# LoRa_RFM98W_Shield.net
KiCad netlist of a schematic drawn in EAGLE
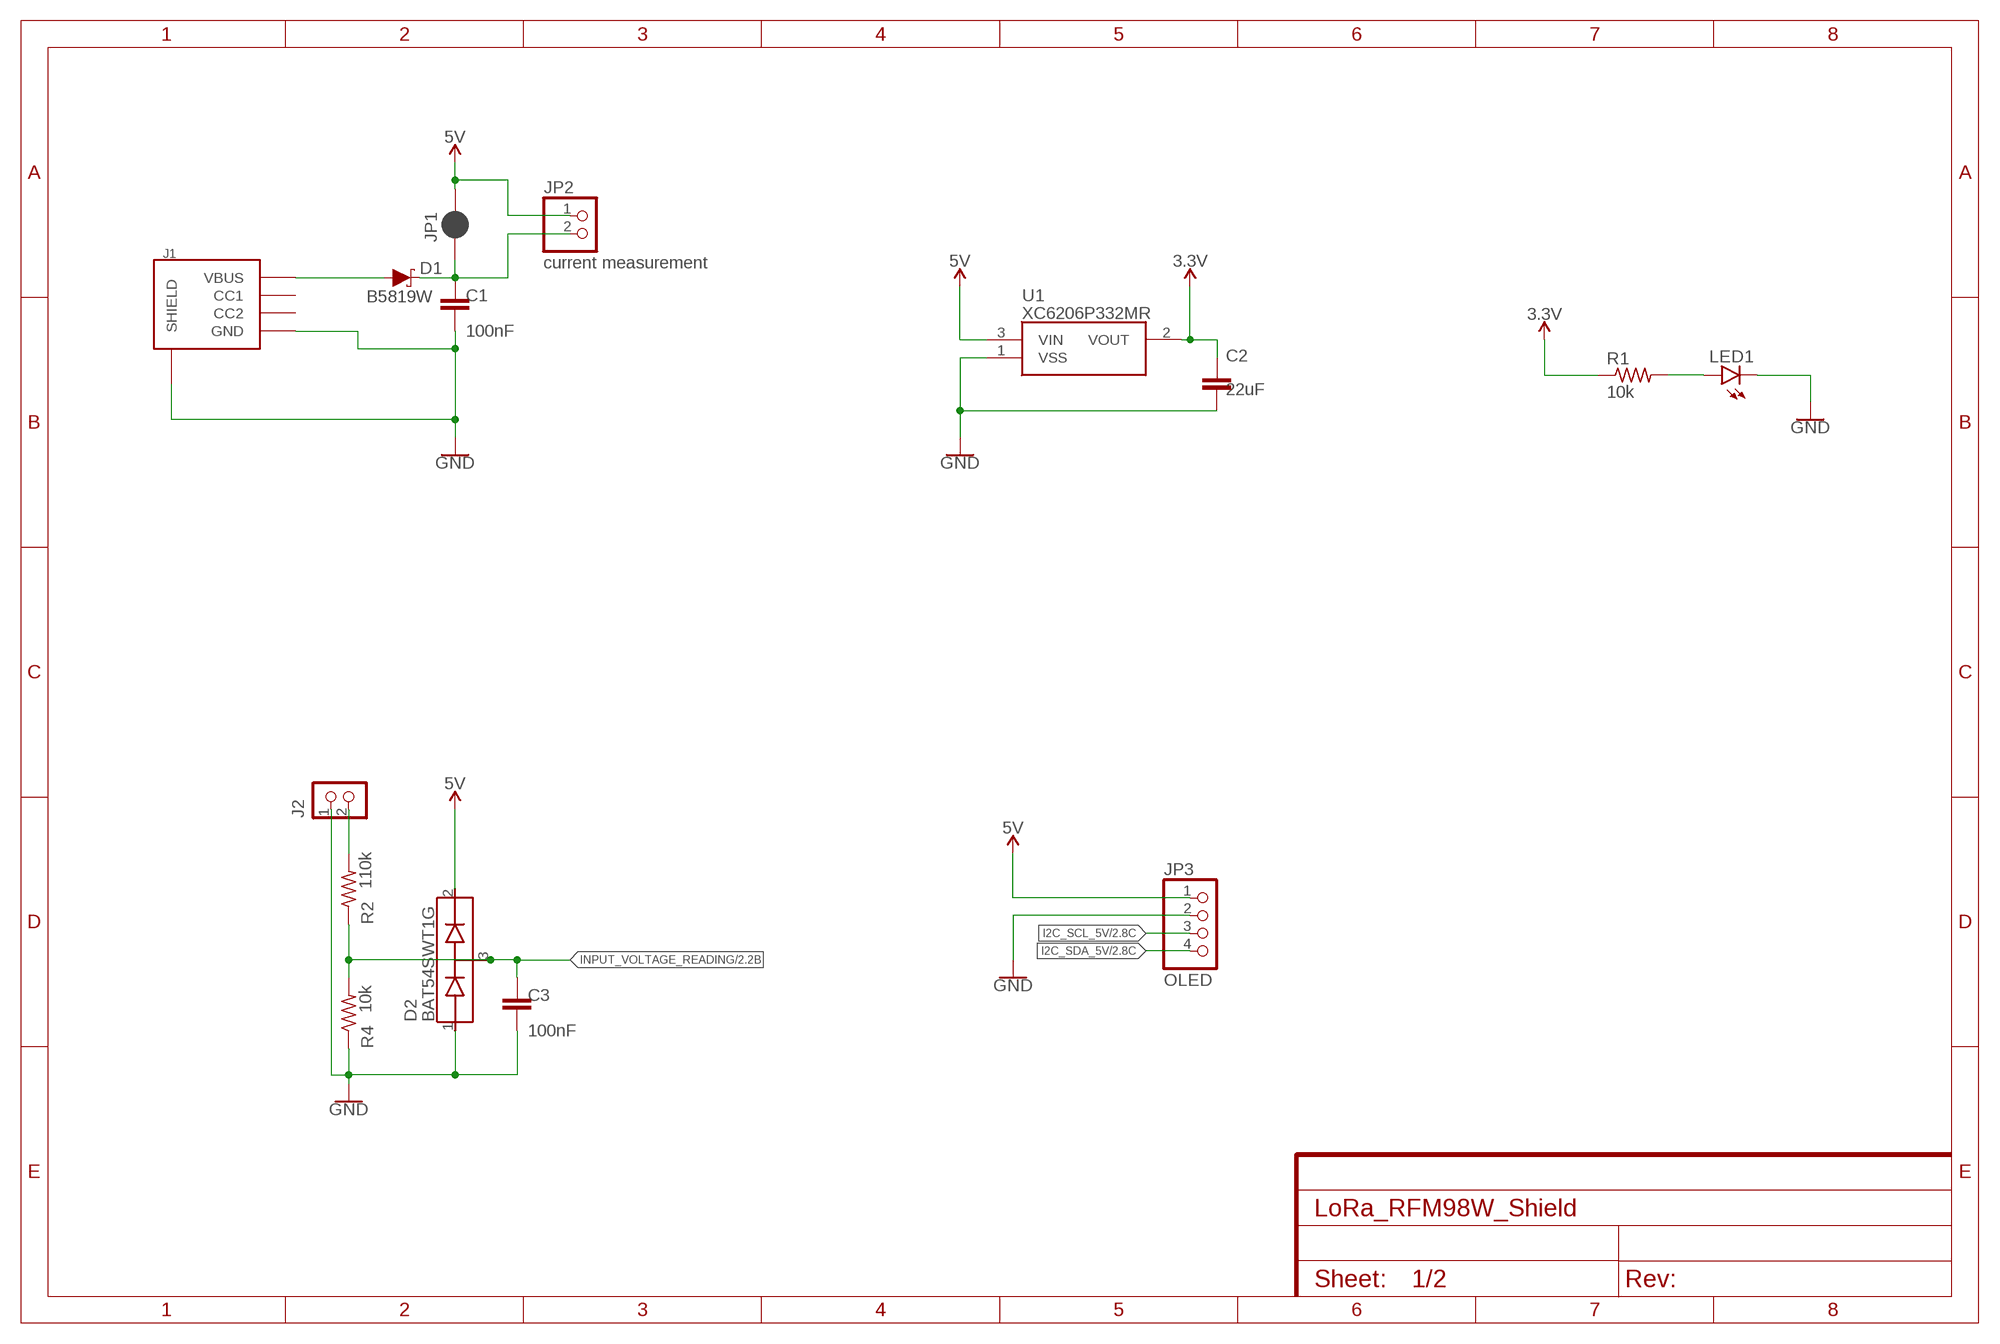
[diagram p0: schematic, sheet 1]
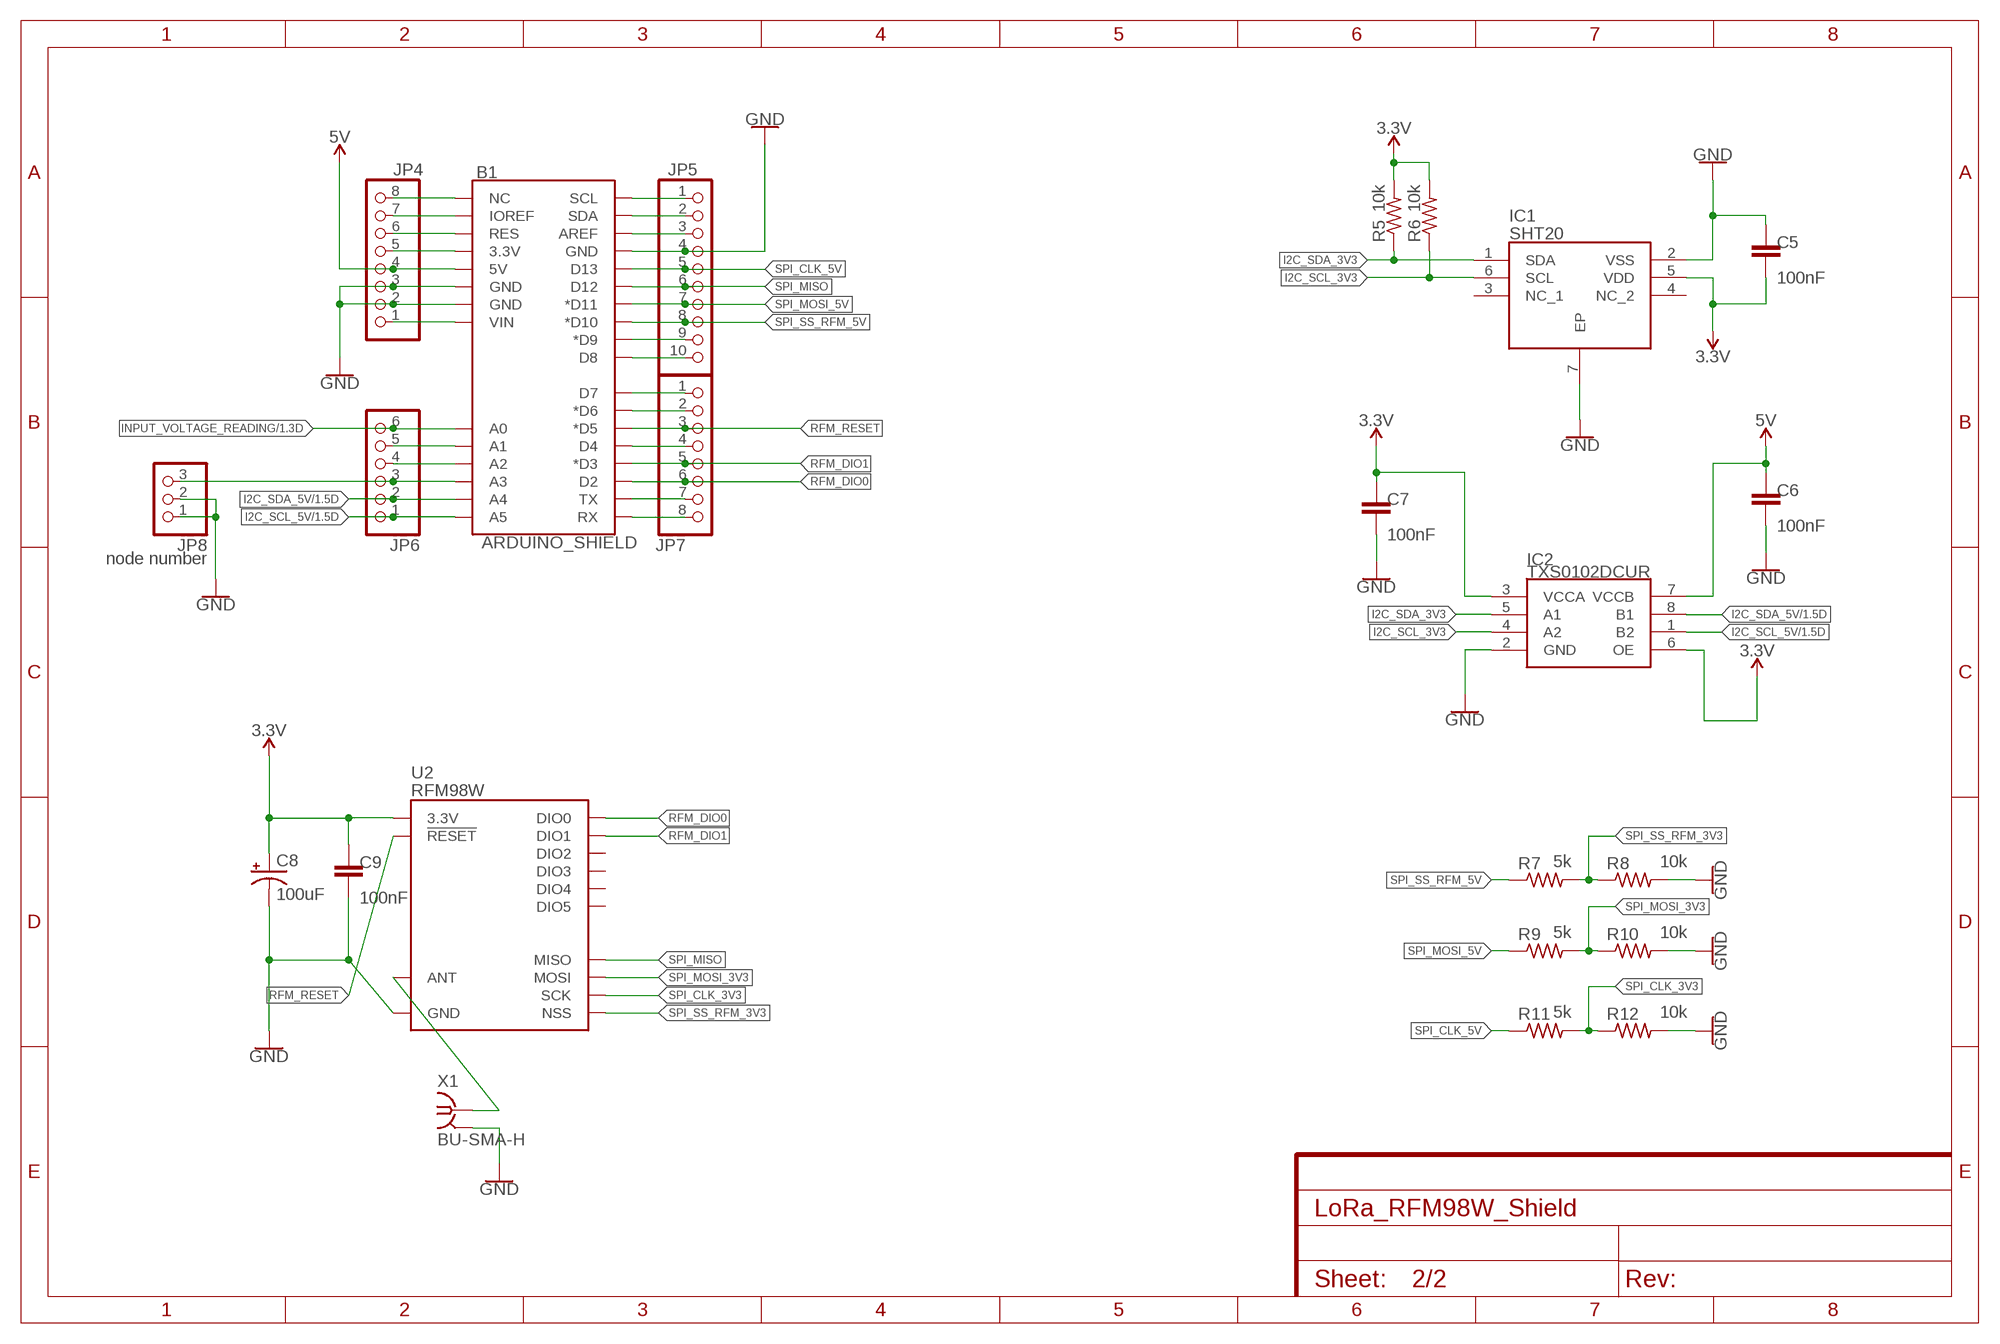
[diagram p1: schematic, sheet 2]

(export (version "E")
  (design (tool "Eeschema 10.0.6"))
  (components
    (comp (ref "B1")
      (value "ARDUINO_SHIELD")
      (footprint "eagle-import:UNO_R3_SHIELD_NOLABELS_LOCK")
      (libsource (lib "eagle-import") (part "ARDUINO_UNO_R3_SHIELDUNO_R3_SHIELD_NOLABELS_LOCK"))
    )
    (comp (ref "C5")
      (value "100nF")
      (footprint "eagle-import:C0603")
      (libsource (lib "eagle-import") (part "C-NON-POLC0603"))
    )
    (comp (ref "C6")
      (value "100nF")
      (footprint "eagle-import:C0603")
      (libsource (lib "eagle-import") (part "C-NON-POLC0603"))
    )
    (comp (ref "C7")
      (value "100nF")
      (footprint "eagle-import:C0603")
      (libsource (lib "eagle-import") (part "C-NON-POLC0603"))
    )
    (comp (ref "C8")
      (value "100uF")
      (footprint "eagle-import:SMC_B")
      (libsource (lib "eagle-import") (part "CPOL-USSMCB"))
    )
    (comp (ref "C9")
      (value "100nF")
      (footprint "eagle-import:C0603")
      (libsource (lib "eagle-import") (part "C-NON-POLC0603"))
    )
    (comp (ref "IC1")
      (value "SHT20")
      (footprint "eagle-import:SON100P300X300X110-7N")
      (fields (field (name "LCSC_PART_NUMBER") "C53865"))
      (libsource (lib "eagle-import") (part "SHT20"))
    )
    (comp (ref "IC2")
      (value "TXS0102DCUR")
      (footprint "eagle-import:SOP50P310X90-8N")
      (fields (field (name "LCSC_PART_NUMBER") "C53434"))
      (libsource (lib "eagle-import") (part "TXS0102DCUR"))
    )
    (comp (ref "JP4")
      (value "PINHD-1X8/OCT")
      (footprint "eagle-import:1X08_OCT")
      (libsource (lib "eagle-import") (part "PINHD-1X8/OCT"))
    )
    (comp (ref "JP5")
      (value "PINHD-1X10/OCT")
      (footprint "eagle-import:1X10_OCT")
      (libsource (lib "eagle-import") (part "PINHD-1X10/OCT"))
    )
    (comp (ref "JP6")
      (value "PINHD-1X6/OCT")
      (footprint "eagle-import:1X06_OCT")
      (libsource (lib "eagle-import") (part "PINHD-1X6/OCT"))
    )
    (comp (ref "JP7")
      (value "PINHD-1X8/OCT")
      (footprint "eagle-import:1X08_OCT")
      (libsource (lib "eagle-import") (part "PINHD-1X8/OCT"))
    )
    (comp (ref "JP8")
      (value "node number")
      (footprint "eagle-import:1X03_OCT")
      (libsource (lib "eagle-import") (part "PINHD-1X3/OCT"))
    )
    (comp (ref "R5")
      (value "10k")
      (footprint "eagle-import:R0603")
      (libsource (lib "eagle-import") (part "RR0603"))
    )
    (comp (ref "R6")
      (value "10k")
      (footprint "eagle-import:R0603")
      (libsource (lib "eagle-import") (part "RR0603"))
    )
    (comp (ref "R7")
      (value "5k")
      (footprint "eagle-import:R0603")
      (libsource (lib "eagle-import") (part "RR0603"))
    )
    (comp (ref "R8")
      (value "10k")
      (footprint "eagle-import:R0603")
      (libsource (lib "eagle-import") (part "RR0603"))
    )
    (comp (ref "R9")
      (value "5k")
      (footprint "eagle-import:R0603")
      (libsource (lib "eagle-import") (part "RR0603"))
    )
    (comp (ref "R10")
      (value "10k")
      (footprint "eagle-import:R0603")
      (libsource (lib "eagle-import") (part "RR0603"))
    )
    (comp (ref "R11")
      (value "5k")
      (footprint "eagle-import:R0603")
      (libsource (lib "eagle-import") (part "RR0603"))
    )
    (comp (ref "R12")
      (value "10k")
      (footprint "eagle-import:R0603")
      (libsource (lib "eagle-import") (part "RR0603"))
    )
    (comp (ref "U2")
      (value "RFM98W")
      (footprint "eagle-import:RFM95_96_97_98W")
      (libsource (lib "eagle-import") (part "RFM95W"))
    )
    (comp (ref "X1")
      (value "BU-SMA-H")
      (footprint "eagle-import:BU-SMA-H")
      (libsource (lib "eagle-import") (part "BU-SMA-H"))
    )
    (comp (ref "C1")
      (value "100nF")
      (footprint "eagle-import:C0603")
      (libsource (lib "eagle-import") (part "C-NON-POLC0603"))
    )
    (comp (ref "C2")
      (value "22uF")
      (footprint "eagle-import:C0805")
      (libsource (lib "eagle-import") (part "C-NON-POLC0805"))
    )
    (comp (ref "C3")
      (value "100nF")
      (footprint "eagle-import:C0603")
      (libsource (lib "eagle-import") (part "C-NON-POLC0603"))
    )
    (comp (ref "D1")
      (value "B5819W")
      (footprint "eagle-import:SOD-123")
      (libsource (lib "eagle-import") (part "DIODE-SCHOTTKY_SOD-123"))
    )
    (comp (ref "D2")
      (value "BAT54SWT1G")
      (footprint "eagle-import:SOT65P220X100-3N")
      (fields (field (name "LCSC_PART_NUMBER") "C78260"))
      (libsource (lib "eagle-import") (part "BAT54SWT1G"))
    )
    (comp (ref "J1")
      (value "USB-TYPE-C-31-M-17")
      (footprint "eagle-import:USB-TYPE-C-31-M-17")
      (libsource (lib "eagle-import") (part "USB-TYPE-C-31-M-17"))
    )
    (comp (ref "J2")
      (value "CON_TERMINAL_BLOCK_02-5MM")
      (footprint "eagle-import:TERMINAL_BLOCK_2P_5")
      (libsource (lib "eagle-import") (part "CON_TERMINAL_BLOCK_02-5MM"))
    )
    (comp (ref "JP1")
      (value "JUMPER-SMT_2_NC_PASTE_SILK")
      (footprint "eagle-import:SMT-JUMPER_2_NC_PASTE_SILK")
      (libsource (lib "eagle-import") (part "JUMPER-SMT_2_NC_PASTE_SILK"))
    )
    (comp (ref "JP2")
      (value "current measurement")
      (footprint "eagle-import:1X02_OCT")
      (libsource (lib "eagle-import") (part "PINHD-1X2/OCT"))
    )
    (comp (ref "JP3")
      (value "OLED")
      (footprint "eagle-import:1X04_OCT")
      (libsource (lib "eagle-import") (part "PINHD-1X4/OCT"))
    )
    (comp (ref "LED1")
      (value "LEDCHIPLED_0805")
      (footprint "eagle-import:CHIPLED_0805")
      (libsource (lib "eagle-import") (part "LEDCHIPLED_0805"))
    )
    (comp (ref "R1")
      (value "10k")
      (footprint "eagle-import:R0603")
      (libsource (lib "eagle-import") (part "RR0603"))
    )
    (comp (ref "R2")
      (value "110k")
      (footprint "eagle-import:R0603")
      (libsource (lib "eagle-import") (part "RR0603"))
    )
    (comp (ref "R4")
      (value "10k")
      (footprint "eagle-import:R0603")
      (libsource (lib "eagle-import") (part "RR0603"))
    )
    (comp (ref "U1")
      (value "XC6206P332MR")
      (footprint "eagle-import:SOT95P280X130-3N")
      (libsource (lib "eagle-import") (part "XC6206P332MR"))
    )
  )
  (nets
    (net (code "1") (name "3.3V") (class "Default")
      (node (ref "C2") (pin "2") (pinfunction "2_2") (pintype "passive"))
      (node (ref "C5") (pin "2") (pinfunction "2_2") (pintype "passive"))
      (node (ref "C7") (pin "1") (pinfunction "1_1") (pintype "passive"))
      (node (ref "C8") (pin "+") (pinfunction "+_+") (pintype "passive"))
      (node (ref "C9") (pin "1") (pinfunction "1_1") (pintype "passive"))
      (node (ref "IC1") (pin "5") (pinfunction "VDD_5") (pintype "bidirectional"))
      (node (ref "IC2") (pin "3") (pinfunction "VCCA_3") (pintype "bidirectional"))
      (node (ref "IC2") (pin "6") (pinfunction "OE_6") (pintype "bidirectional"))
      (node (ref "R1") (pin "1") (pinfunction "1_1") (pintype "passive"))
      (node (ref "R5") (pin "2") (pinfunction "2_2") (pintype "passive"))
      (node (ref "R6") (pin "2") (pinfunction "2_2") (pintype "passive"))
      (node (ref "U1") (pin "2") (pinfunction "VOUT_2") (pintype "output"))
      (node (ref "U2") (pin "3.3V") (pinfunction "3.3V_3.3V") (pintype "bidirectional"))
    )
    (net (code "2") (name "5V") (class "Default")
      (node (ref "B1") (pin "5V") (pinfunction "5V_5V") (pintype "bidirectional"))
      (node (ref "C6") (pin "1") (pinfunction "1_1") (pintype "passive"))
      (node (ref "D2") (pin "2") (pinfunction "CATHODE_2") (pintype "bidirectional"))
      (node (ref "IC2") (pin "7") (pinfunction "VCCB_7") (pintype "bidirectional"))
      (node (ref "JP1") (pin "2") (pinfunction "2_2") (pintype "passive"))
      (node (ref "JP2") (pin "1") (pinfunction "1_1") (pintype "passive"))
      (node (ref "JP3") (pin "1") (pinfunction "1_1") (pintype "passive"))
      (node (ref "JP4") (pin "4") (pinfunction "4_4") (pintype "passive"))
      (node (ref "U1") (pin "3") (pinfunction "VIN_3") (pintype "input"))
    )
    (net (code "3") (name "GND") (class "Default")
      (node (ref "B1") (pin "GND@0") (pinfunction "GND_GND@0") (pintype "bidirectional"))
      (node (ref "B1") (pin "GND@1") (pinfunction "GND_GND@1") (pintype "bidirectional"))
      (node (ref "B1") (pin "GND@2") (pinfunction "GND_GND@2") (pintype "bidirectional"))
      (node (ref "C1") (pin "2") (pinfunction "2_2") (pintype "passive"))
      (node (ref "C2") (pin "1") (pinfunction "1_1") (pintype "passive"))
      (node (ref "C3") (pin "2") (pinfunction "2_2") (pintype "passive"))
      (node (ref "C5") (pin "1") (pinfunction "1_1") (pintype "passive"))
      (node (ref "C6") (pin "2") (pinfunction "2_2") (pintype "passive"))
      (node (ref "C7") (pin "2") (pinfunction "2_2") (pintype "passive"))
      (node (ref "C8") (pin "-") (pinfunction "-_-") (pintype "passive"))
      (node (ref "C9") (pin "2") (pinfunction "2_2") (pintype "passive"))
      (node (ref "D2") (pin "1") (pinfunction "ANODE_1") (pintype "bidirectional"))
      (node (ref "IC1") (pin "2") (pinfunction "VSS_2") (pintype "bidirectional"))
      (node (ref "IC1") (pin "7") (pinfunction "EP_7") (pintype "bidirectional"))
      (node (ref "IC2") (pin "2") (pinfunction "GND_2") (pintype "bidirectional"))
      (node (ref "J1") (pin "GND") (pinfunction "GND_GND") (pintype "bidirectional"))
      (node (ref "J1") (pin "GND_2") (pinfunction "GND_GND_2") (pintype "bidirectional"))
      (node (ref "J1") (pin "SHLD-B1") (pinfunction "SHIELD_SHLD-B1") (pintype "bidirectional"))
      (node (ref "J1") (pin "SHLD-B2") (pinfunction "SHIELD_SHLD-B2") (pintype "bidirectional"))
      (node (ref "J1") (pin "SHLD-B3") (pinfunction "SHIELD_SHLD-B3") (pintype "bidirectional"))
      (node (ref "J1") (pin "SHLD-B4") (pinfunction "SHIELD_SHLD-B4") (pintype "bidirectional"))
      (node (ref "J1") (pin "SHLD-T1") (pinfunction "SHIELD_SHLD-T1") (pintype "bidirectional"))
      (node (ref "J1") (pin "SHLD-T2") (pinfunction "SHIELD_SHLD-T2") (pintype "bidirectional"))
      (node (ref "J1") (pin "SHLD-T3") (pinfunction "SHIELD_SHLD-T3") (pintype "bidirectional"))
      (node (ref "J1") (pin "SHLD-T4") (pinfunction "SHIELD_SHLD-T4") (pintype "bidirectional"))
      (node (ref "J2") (pin "1") (pinfunction "1_1") (pintype "passive"))
      (node (ref "JP3") (pin "2") (pinfunction "2_2") (pintype "passive"))
      (node (ref "JP4") (pin "2") (pinfunction "2_2") (pintype "passive"))
      (node (ref "JP4") (pin "3") (pinfunction "3_3") (pintype "passive"))
      (node (ref "JP5") (pin "4") (pinfunction "4_4") (pintype "passive"))
      (node (ref "JP8") (pin "1") (pinfunction "1_1") (pintype "passive"))
      (node (ref "JP8") (pin "2") (pinfunction "2_2") (pintype "passive"))
      (node (ref "LED1") (pin "C") (pinfunction "C_C") (pintype "passive"))
      (node (ref "R10") (pin "2") (pinfunction "2_2") (pintype "passive"))
      (node (ref "R12") (pin "2") (pinfunction "2_2") (pintype "passive"))
      (node (ref "R4") (pin "1") (pinfunction "1_1") (pintype "passive"))
      (node (ref "R8") (pin "2") (pinfunction "2_2") (pintype "passive"))
      (node (ref "U1") (pin "1") (pinfunction "VSS_1") (pintype "power_in"))
      (node (ref "U2") (pin "GND@1") (pinfunction "GND_GND@1") (pintype "bidirectional"))
      (node (ref "U2") (pin "GND@2") (pinfunction "GND_GND@2") (pintype "bidirectional"))
      (node (ref "U2") (pin "GND@3") (pinfunction "GND_GND@3") (pintype "bidirectional"))
      (node (ref "X1") (pin "2") (pinfunction "2_2") (pintype "passive"))
      (node (ref "X1") (pin "3") (pinfunction "2_3") (pintype "passive"))
      (node (ref "X1") (pin "4") (pinfunction "2_4") (pintype "passive"))
      (node (ref "X1") (pin "5") (pinfunction "2_5") (pintype "passive"))
    )
    (net (code "4") (name "I2C_SCL_3V3") (class "Default")
      (node (ref "IC1") (pin "6") (pinfunction "SCL_6") (pintype "bidirectional"))
      (node (ref "IC2") (pin "4") (pinfunction "A2_4") (pintype "bidirectional"))
      (node (ref "R6") (pin "1") (pinfunction "1_1") (pintype "passive"))
    )
    (net (code "5") (name "I2C_SCL_5V") (class "Default")
      (node (ref "B1") (pin "A5") (pinfunction "A5_A5") (pintype "bidirectional"))
      (node (ref "IC2") (pin "1") (pinfunction "B2_1") (pintype "bidirectional"))
      (node (ref "JP3") (pin "3") (pinfunction "3_3") (pintype "passive"))
      (node (ref "JP6") (pin "1") (pinfunction "1_1") (pintype "passive"))
    )
    (net (code "6") (name "I2C_SDA_3V3") (class "Default")
      (node (ref "IC1") (pin "1") (pinfunction "SDA_1") (pintype "bidirectional"))
      (node (ref "IC2") (pin "5") (pinfunction "A1_5") (pintype "bidirectional"))
      (node (ref "R5") (pin "1") (pinfunction "1_1") (pintype "passive"))
    )
    (net (code "7") (name "I2C_SDA_5V") (class "Default")
      (node (ref "B1") (pin "A4") (pinfunction "A4_A4") (pintype "bidirectional"))
      (node (ref "IC2") (pin "8") (pinfunction "B1_8") (pintype "bidirectional"))
      (node (ref "JP3") (pin "4") (pinfunction "4_4") (pintype "passive"))
      (node (ref "JP6") (pin "2") (pinfunction "2_2") (pintype "passive"))
    )
    (net (code "8") (name "INPUT_VOLTAGE_READING") (class "Default")
      (node (ref "B1") (pin "A0") (pinfunction "A0_A0") (pintype "bidirectional"))
      (node (ref "C3") (pin "1") (pinfunction "1_1") (pintype "passive"))
      (node (ref "D2") (pin "3") (pinfunction "CATHODE-ANODE_3") (pintype "bidirectional"))
      (node (ref "JP6") (pin "6") (pinfunction "6_6") (pintype "passive"))
      (node (ref "R2") (pin "1") (pinfunction "1_1") (pintype "passive"))
      (node (ref "R4") (pin "2") (pinfunction "2_2") (pintype "passive"))
    )
    (net (code "9") (name "Net-(B1-*D6)") (class "Default")
      (node (ref "B1") (pin "D6") (pinfunction "*D6_D6") (pintype "bidirectional"))
      (node (ref "JP7") (pin "2") (pinfunction "2_2") (pintype "passive"))
    )
    (net (code "10") (name "Net-(B1-*D9)") (class "Default")
      (node (ref "B1") (pin "D9") (pinfunction "*D9_D9") (pintype "bidirectional"))
      (node (ref "JP5") (pin "9") (pinfunction "9_9") (pintype "passive"))
    )
    (net (code "11") (name "Net-(B1-Pad3.3V)") (class "Default")
      (node (ref "B1") (pin "3.3V") (pinfunction "3.3V_3.3V") (pintype "bidirectional"))
      (node (ref "JP4") (pin "5") (pinfunction "5_5") (pintype "passive"))
    )
    (net (code "12") (name "Net-(B1-PadA1)") (class "Default")
      (node (ref "B1") (pin "A1") (pinfunction "A1_A1") (pintype "bidirectional"))
      (node (ref "JP6") (pin "5") (pinfunction "5_5") (pintype "passive"))
    )
    (net (code "13") (name "Net-(B1-PadA2)") (class "Default")
      (node (ref "B1") (pin "A2") (pinfunction "A2_A2") (pintype "bidirectional"))
      (node (ref "JP6") (pin "4") (pinfunction "4_4") (pintype "passive"))
    )
    (net (code "14") (name "Net-(B1-PadA3)") (class "Default")
      (node (ref "B1") (pin "A3") (pinfunction "A3_A3") (pintype "bidirectional"))
      (node (ref "JP6") (pin "3") (pinfunction "3_3") (pintype "passive"))
      (node (ref "JP8") (pin "3") (pinfunction "3_3") (pintype "passive"))
    )
    (net (code "15") (name "Net-(B1-PadAREF)") (class "Default")
      (node (ref "B1") (pin "AREF") (pinfunction "AREF_AREF") (pintype "bidirectional"))
      (node (ref "JP5") (pin "3") (pinfunction "3_3") (pintype "passive"))
    )
    (net (code "16") (name "Net-(B1-PadD4)") (class "Default")
      (node (ref "B1") (pin "D4") (pinfunction "D4_D4") (pintype "bidirectional"))
      (node (ref "JP7") (pin "4") (pinfunction "4_4") (pintype "passive"))
    )
    (net (code "17") (name "Net-(B1-PadD7)") (class "Default")
      (node (ref "B1") (pin "D7") (pinfunction "D7_D7") (pintype "bidirectional"))
      (node (ref "JP7") (pin "1") (pinfunction "1_1") (pintype "passive"))
    )
    (net (code "18") (name "Net-(B1-PadD8)") (class "Default")
      (node (ref "B1") (pin "D8") (pinfunction "D8_D8") (pintype "bidirectional"))
      (node (ref "JP5") (pin "10") (pinfunction "10_10") (pintype "passive"))
    )
    (net (code "19") (name "Net-(B1-PadIOREF)") (class "Default")
      (node (ref "B1") (pin "IOREF") (pinfunction "IOREF_IOREF") (pintype "bidirectional"))
      (node (ref "JP4") (pin "7") (pinfunction "7_7") (pintype "passive"))
    )
    (net (code "20") (name "Net-(B1-PadNC)") (class "Default")
      (node (ref "B1") (pin "NC") (pinfunction "NC_NC") (pintype "bidirectional"))
      (node (ref "JP4") (pin "8") (pinfunction "8_8") (pintype "passive"))
    )
    (net (code "21") (name "Net-(B1-PadRES)") (class "Default")
      (node (ref "B1") (pin "RES") (pinfunction "RES_RES") (pintype "bidirectional"))
      (node (ref "JP4") (pin "6") (pinfunction "6_6") (pintype "passive"))
    )
    (net (code "22") (name "Net-(B1-PadRX)") (class "Default")
      (node (ref "B1") (pin "RX") (pinfunction "RX_RX") (pintype "bidirectional"))
      (node (ref "JP7") (pin "8") (pinfunction "8_8") (pintype "passive"))
    )
    (net (code "23") (name "Net-(B1-PadSCL)") (class "Default")
      (node (ref "B1") (pin "SCL") (pinfunction "SCL_SCL") (pintype "bidirectional"))
      (node (ref "JP5") (pin "1") (pinfunction "1_1") (pintype "passive"))
    )
    (net (code "24") (name "Net-(B1-PadSDA)") (class "Default")
      (node (ref "B1") (pin "SDA") (pinfunction "SDA_SDA") (pintype "bidirectional"))
      (node (ref "JP5") (pin "2") (pinfunction "2_2") (pintype "passive"))
    )
    (net (code "25") (name "Net-(B1-PadTX)") (class "Default")
      (node (ref "B1") (pin "TX") (pinfunction "TX_TX") (pintype "bidirectional"))
      (node (ref "JP7") (pin "7") (pinfunction "7_7") (pintype "passive"))
    )
    (net (code "26") (name "Net-(B1-PadVIN)") (class "Default")
      (node (ref "B1") (pin "VIN") (pinfunction "VIN_VIN") (pintype "bidirectional"))
      (node (ref "JP4") (pin "1") (pinfunction "1_1") (pintype "passive"))
    )
    (net (code "27") (name "Net-(C1-Pad1)") (class "Default")
      (node (ref "C1") (pin "1") (pinfunction "1_1") (pintype "passive"))
      (node (ref "D1") (pin "C") (pinfunction "C_C") (pintype "passive"))
      (node (ref "JP1") (pin "1") (pinfunction "1_1") (pintype "passive"))
      (node (ref "JP2") (pin "2") (pinfunction "2_2") (pintype "passive"))
    )
    (net (code "28") (name "Net-(D1-PadA)") (class "Default")
      (node (ref "D1") (pin "A") (pinfunction "A_A") (pintype "passive"))
      (node (ref "J1") (pin "VBUS") (pinfunction "VBUS_VBUS") (pintype "bidirectional"))
      (node (ref "J1") (pin "VBUS_2") (pinfunction "VBUS_VBUS_2") (pintype "bidirectional"))
    )
    (net (code "29") (name "Net-(J2-Pad2)") (class "Default")
      (node (ref "J2") (pin "2") (pinfunction "2_2") (pintype "passive"))
      (node (ref "R2") (pin "2") (pinfunction "2_2") (pintype "passive"))
    )
    (net (code "30") (name "Net-(LED1-PadA)") (class "Default")
      (node (ref "LED1") (pin "A") (pinfunction "A_A") (pintype "passive"))
      (node (ref "R1") (pin "2") (pinfunction "2_2") (pintype "passive"))
    )
    (net (code "31") (name "Net-(U2-PadANT)") (class "Default")
      (node (ref "U2") (pin "ANT") (pinfunction "ANT_ANT") (pintype "bidirectional"))
      (node (ref "X1") (pin "1") (pinfunction "1_1") (pintype "passive"))
    )
    (net (code "32") (name "RFM_DIO0") (class "Default")
      (node (ref "B1") (pin "D2") (pinfunction "D2_D2") (pintype "bidirectional"))
      (node (ref "JP7") (pin "6") (pinfunction "6_6") (pintype "passive"))
      (node (ref "U2") (pin "DIO0") (pinfunction "DIO0_DIO0") (pintype "bidirectional"))
    )
    (net (code "33") (name "RFM_DIO1") (class "Default")
      (node (ref "B1") (pin "D3") (pinfunction "*D3_D3") (pintype "bidirectional"))
      (node (ref "JP7") (pin "5") (pinfunction "5_5") (pintype "passive"))
      (node (ref "U2") (pin "DIO1") (pinfunction "DIO1_DIO1") (pintype "bidirectional"))
    )
    (net (code "34") (name "RFM_RESET") (class "Default")
      (node (ref "B1") (pin "D5") (pinfunction "*D5_D5") (pintype "bidirectional"))
      (node (ref "JP7") (pin "3") (pinfunction "3_3") (pintype "passive"))
      (node (ref "U2") (pin "!RESET") (pinfunction "~{RESET}_!RESET") (pintype "bidirectional"))
    )
    (net (code "35") (name "SPI_CLK_3V3") (class "Default")
      (node (ref "R11") (pin "2") (pinfunction "2_2") (pintype "passive"))
      (node (ref "R12") (pin "1") (pinfunction "1_1") (pintype "passive"))
      (node (ref "U2") (pin "SCK") (pinfunction "SCK_SCK") (pintype "bidirectional"))
    )
    (net (code "36") (name "SPI_CLK_5V") (class "Default")
      (node (ref "B1") (pin "D13") (pinfunction "D13_D13") (pintype "bidirectional"))
      (node (ref "JP5") (pin "5") (pinfunction "5_5") (pintype "passive"))
      (node (ref "R11") (pin "1") (pinfunction "1_1") (pintype "passive"))
    )
    (net (code "37") (name "SPI_MISO") (class "Default")
      (node (ref "B1") (pin "D12") (pinfunction "D12_D12") (pintype "bidirectional"))
      (node (ref "JP5") (pin "6") (pinfunction "6_6") (pintype "passive"))
      (node (ref "U2") (pin "MISO") (pinfunction "MISO_MISO") (pintype "bidirectional"))
    )
    (net (code "38") (name "SPI_MOSI_3V3") (class "Default")
      (node (ref "R10") (pin "1") (pinfunction "1_1") (pintype "passive"))
      (node (ref "R9") (pin "2") (pinfunction "2_2") (pintype "passive"))
      (node (ref "U2") (pin "MOSI") (pinfunction "MOSI_MOSI") (pintype "bidirectional"))
    )
    (net (code "39") (name "SPI_MOSI_5V") (class "Default")
      (node (ref "B1") (pin "D11") (pinfunction "*D11_D11") (pintype "bidirectional"))
      (node (ref "JP5") (pin "7") (pinfunction "7_7") (pintype "passive"))
      (node (ref "R9") (pin "1") (pinfunction "1_1") (pintype "passive"))
    )
    (net (code "40") (name "SPI_SS_RFM_3V3") (class "Default")
      (node (ref "R7") (pin "2") (pinfunction "2_2") (pintype "passive"))
      (node (ref "R8") (pin "1") (pinfunction "1_1") (pintype "passive"))
      (node (ref "U2") (pin "NSS") (pinfunction "NSS_NSS") (pintype "bidirectional"))
    )
    (net (code "41") (name "SPI_SS_RFM_5V") (class "Default")
      (node (ref "B1") (pin "D10") (pinfunction "*D10_D10") (pintype "bidirectional"))
      (node (ref "JP5") (pin "8") (pinfunction "8_8") (pintype "passive"))
      (node (ref "R7") (pin "1") (pinfunction "1_1") (pintype "passive"))
    )
    (net (code "42") (name "unconnected-(IC1-NC_1-Pad3)") (class "Default")
      (node (ref "IC1") (pin "3") (pinfunction "NC_1_3") (pintype "bidirectional"))
    )
    (net (code "43") (name "unconnected-(IC1-NC_2-Pad4)") (class "Default")
      (node (ref "IC1") (pin "4") (pinfunction "NC_2_4") (pintype "bidirectional"))
    )
    (net (code "44") (name "unconnected-(J1-PadCC1)") (class "Default")
      (node (ref "J1") (pin "CC1") (pinfunction "CC1_CC1") (pintype "bidirectional"))
    )
    (net (code "45") (name "unconnected-(J1-PadCC2)") (class "Default")
      (node (ref "J1") (pin "CC2") (pinfunction "CC2_CC2") (pintype "bidirectional"))
    )
    (net (code "46") (name "unconnected-(U2-PadDIO2)") (class "Default")
      (node (ref "U2") (pin "DIO2") (pinfunction "DIO2_DIO2") (pintype "bidirectional"))
    )
    (net (code "47") (name "unconnected-(U2-PadDIO3)") (class "Default")
      (node (ref "U2") (pin "DIO3") (pinfunction "DIO3_DIO3") (pintype "bidirectional"))
    )
    (net (code "48") (name "unconnected-(U2-PadDIO4)") (class "Default")
      (node (ref "U2") (pin "DIO4") (pinfunction "DIO4_DIO4") (pintype "bidirectional"))
    )
    (net (code "49") (name "unconnected-(U2-PadDIO5)") (class "Default")
      (node (ref "U2") (pin "DIO5") (pinfunction "DIO5_DIO5") (pintype "bidirectional"))
    )
  )
)
